# ZYNQ_PL_Bank_35.net
KiCad netlist of a schematic drawn in Altium Designer
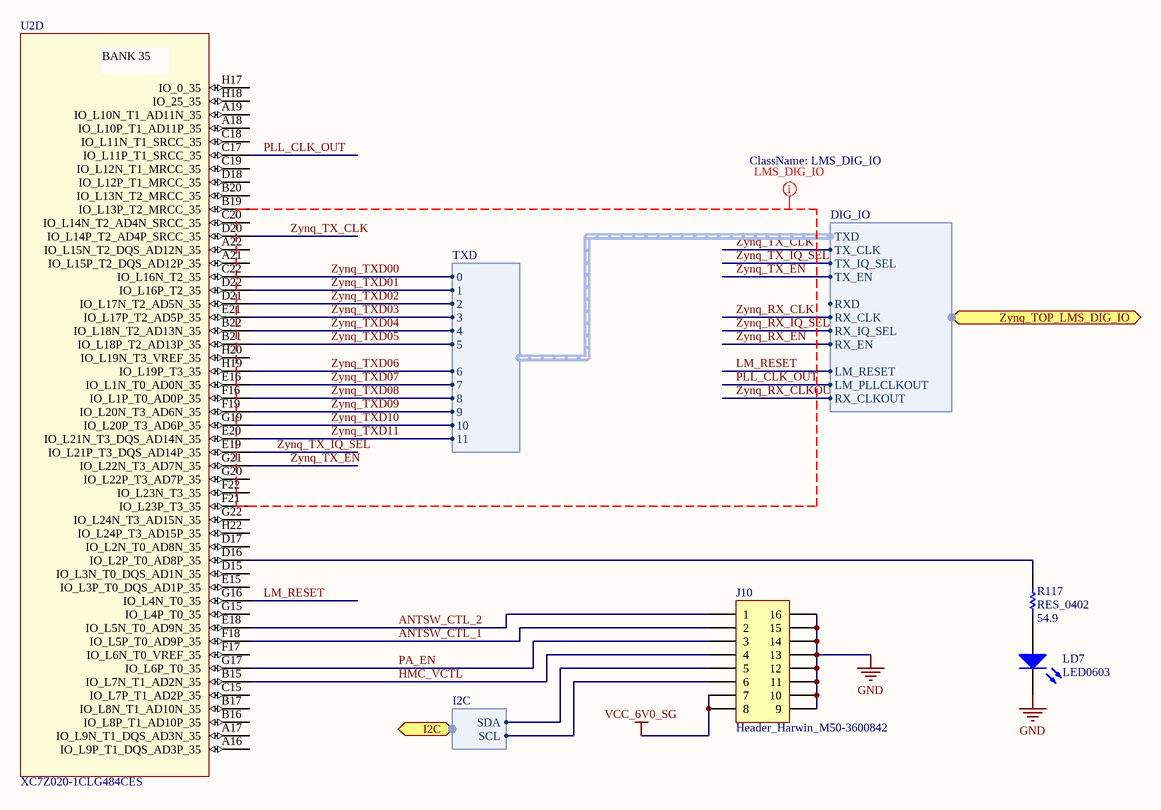
[diagram p0: ZYNQ_PL_Bank_35.SchDoc]

(export (version "E")
  (design (tool "Eeschema 10.0.6"))
  (components
    (comp (ref "J10")
      (value "Header_Harwin_M50-3600842")
      (footprint "Header_Harwin_M50-3600842_16-pos")
      (description "CONN HDR 1.27MM SMD AU 16POS")
      (fields (field (name "PART NUMBER") "M50-3600842") (field (name "MANUFACTURER") "Harwin Inc"))
      (libsource (lib "COMRAD_Database") (part "Header_Harwin_M50-3600842"))
    )
    (comp (ref "LD7")
      (value "LED0603")
      (footprint "LED0603(1608)_HSMG-C190")
      (description "LED 570NM GREEN DIFF 0603 SMD")
      (fields (field (name "PART NUMBER") "\"HSMG-C190\"") (field (name "MANUFACTURER") "Avago"))
      (libsource (lib "COMRAD_Database") (part "LED0603"))
    )
    (comp (ref "R117")
      (value "RES_0402")
      (footprint "RESC0402(1005)_N")
      (description "RES 54.9 OHM 1/10W 1% 0402 SMD")
      (fields
        (field (name "ALTIUM_VALUE") "54.9")
        (field (name "PART NUMBER") "ERJ-2RKF54R9X")
        (field (name "MANUFACTURER") "Panasonic Electronic Components")
      )
      (libsource (lib "COMRAD_Database") (part "RES_0402"))
    )
    (comp (ref "U2")
      (value "XC7Z020-1CLG484CES")
      (footprint "ZYNQ_xc7z020clg484pkg_BGA-484")
      (description "XC7Z020-1CLG484CES, Zynq-7000 All Programmable SoC")
      (fields (field (name "MANUFACTURER") "Xilinx"))
      (libsource (lib "COMRAD_Database") (part "ZYNQ_XC7Z020CLG484PKG"))
    )
  )
  (nets
    (net (code "4") (name "/ANTSW_CTL_1") (class "Default")
      (node (ref "J10") (pin "2") (pinfunction "2_2") (pintype "passive"))
      (node (ref "U2") (pin "F18") (pinfunction "IO_L5P_T0_AD9P_35_F18") (pintype "bidirectional"))
    )
    (net (code "5") (name "/ANTSW_CTL_2") (class "Default")
      (node (ref "J10") (pin "1") (pinfunction "1_1") (pintype "passive"))
      (node (ref "U2") (pin "E18") (pinfunction "IO_L5N_T0_AD9N_35_E18") (pintype "bidirectional"))
    )
    (net (code "6") (name "/HMC_VCTL") (class "Default")
      (node (ref "J10") (pin "4") (pinfunction "4_4") (pintype "passive"))
      (node (ref "U2") (pin "B15") (pinfunction "IO_L7N_T1_AD2N_35_B15") (pintype "bidirectional"))
    )
    (net (code "7") (name "/LM_RESET") (class "Default")
      (node (ref "U2") (pin "G16") (pinfunction "IO_L4N_T0_35_G16") (pintype "bidirectional"))
    )
    (net (code "8") (name "/PA_EN") (class "Default")
      (node (ref "J10") (pin "3") (pinfunction "3_3") (pintype "passive"))
      (node (ref "U2") (pin "G17") (pinfunction "IO_L6P_T0_35_G17") (pintype "bidirectional"))
    )
    (net (code "9") (name "/PLL_CLK_OUT") (class "Default")
      (node (ref "U2") (pin "C17") (pinfunction "IO_L11P_T1_SRCC_35_C17") (pintype "bidirectional"))
    )
    (net (code "10") (name "/SCL") (class "Default")
      (node (ref "J10") (pin "6") (pinfunction "6_6") (pintype "passive"))
    )
    (net (code "11") (name "/SDA") (class "Default")
      (node (ref "J10") (pin "5") (pinfunction "5_5") (pintype "passive"))
    )
    (net (code "17") (name "/Zynq_TXD00") (class "Default")
      (node (ref "U2") (pin "C22") (pinfunction "IO_L16N_T2_35_C22") (pintype "bidirectional"))
    )
    (net (code "18") (name "/Zynq_TXD01") (class "Default")
      (node (ref "U2") (pin "D22") (pinfunction "IO_L16P_T2_35_D22") (pintype "bidirectional"))
    )
    (net (code "19") (name "/Zynq_TXD02") (class "Default")
      (node (ref "U2") (pin "D21") (pinfunction "IO_L17N_T2_AD5N_35_D21") (pintype "bidirectional"))
    )
    (net (code "20") (name "/Zynq_TXD03") (class "Default")
      (node (ref "U2") (pin "E21") (pinfunction "IO_L17P_T2_AD5P_35_E21") (pintype "bidirectional"))
    )
    (net (code "21") (name "/Zynq_TXD04") (class "Default")
      (node (ref "U2") (pin "B22") (pinfunction "IO_L18N_T2_AD13N_35_B22") (pintype "bidirectional"))
    )
    (net (code "22") (name "/Zynq_TXD05") (class "Default")
      (node (ref "U2") (pin "B21") (pinfunction "IO_L18P_T2_AD13P_35_B21") (pintype "bidirectional"))
    )
    (net (code "23") (name "/Zynq_TXD06") (class "Default")
      (node (ref "U2") (pin "H19") (pinfunction "IO_L19P_T3_35_H19") (pintype "bidirectional"))
    )
    (net (code "24") (name "/Zynq_TXD07") (class "Default")
      (node (ref "U2") (pin "E16") (pinfunction "IO_L1N_T0_AD0N_35_E16") (pintype "bidirectional"))
    )
    (net (code "25") (name "/Zynq_TXD08") (class "Default")
      (node (ref "U2") (pin "F16") (pinfunction "IO_L1P_T0_AD0P_35_F16") (pintype "bidirectional"))
    )
    (net (code "26") (name "/Zynq_TXD09") (class "Default")
      (node (ref "U2") (pin "F19") (pinfunction "IO_L20N_T3_AD6N_35_F19") (pintype "bidirectional"))
    )
    (net (code "27") (name "/Zynq_TXD10") (class "Default")
      (node (ref "U2") (pin "G19") (pinfunction "IO_L20P_T3_AD6P_35_G19") (pintype "bidirectional"))
    )
    (net (code "28") (name "/Zynq_TXD11") (class "Default")
      (node (ref "U2") (pin "E20") (pinfunction "IO_L21N_T3_DQS_AD14N_35_E20") (pintype "bidirectional"))
    )
    (net (code "29") (name "/Zynq_TX_CLK") (class "Default")
      (node (ref "U2") (pin "D20") (pinfunction "IO_L14P_T2_AD4P_SRCC_35_D20") (pintype "bidirectional"))
    )
    (net (code "30") (name "/Zynq_TX_EN") (class "Default")
      (node (ref "U2") (pin "G21") (pinfunction "IO_L22N_T3_AD7N_35_G21") (pintype "bidirectional"))
    )
    (net (code "31") (name "/Zynq_TX_IQ_SEL") (class "Default")
      (node (ref "U2") (pin "E19") (pinfunction "IO_L21P_T3_DQS_AD14P_35_E19") (pintype "bidirectional"))
    )
    (net (code "34") (name "GND") (class "Default")
      (node (ref "J10") (pin "10") (pinfunction "10_10") (pintype "passive"))
      (node (ref "J10") (pin "11") (pinfunction "11_11") (pintype "passive"))
      (node (ref "J10") (pin "12") (pinfunction "12_12") (pintype "passive"))
      (node (ref "J10") (pin "13") (pinfunction "13_13") (pintype "passive"))
      (node (ref "J10") (pin "14") (pinfunction "14_14") (pintype "passive"))
      (node (ref "J10") (pin "15") (pinfunction "15_15") (pintype "passive"))
      (node (ref "J10") (pin "16") (pinfunction "16_16") (pintype "passive"))
      (node (ref "J10") (pin "9") (pinfunction "9_9") (pintype "passive"))
      (node (ref "LD7") (pin "1") (pinfunction "K_1") (pintype "passive"))
    )
    (net (code "35") (name "Net-(LD7-A)") (class "Default")
      (node (ref "LD7") (pin "2") (pinfunction "A_2") (pintype "passive"))
      (node (ref "R117") (pin "1") (pinfunction "1_1") (pintype "passive"))
    )
    (net (code "36") (name "Net-(U2D-IO_L2P_T0_AD8P_35)") (class "Default")
      (node (ref "R117") (pin "2") (pinfunction "2_2") (pintype "passive"))
      (node (ref "U2") (pin "D16") (pinfunction "IO_L2P_T0_AD8P_35_D16") (pintype "bidirectional"))
    )
    (net (code "37") (name "VCC_6V0_SG") (class "Default")
      (node (ref "J10") (pin "7") (pinfunction "7_7") (pintype "passive"))
      (node (ref "J10") (pin "8") (pinfunction "8_8") (pintype "passive"))
    )
    (net (code "38") (name "unconnected-(U2D-IO_0_35-PadH17)") (class "Default")
      (node (ref "U2") (pin "H17") (pinfunction "IO_0_35_H17") (pintype "bidirectional"))
    )
    (net (code "39") (name "unconnected-(U2D-IO_25_35-PadH18)") (class "Default")
      (node (ref "U2") (pin "H18") (pinfunction "IO_25_35_H18") (pintype "bidirectional"))
    )
    (net (code "40") (name "unconnected-(U2D-IO_L2N_T0_AD8N_35-PadD17)") (class "Default")
      (node (ref "U2") (pin "D17") (pinfunction "IO_L2N_T0_AD8N_35_D17") (pintype "bidirectional"))
    )
    (net (code "41") (name "unconnected-(U2D-IO_L3N_T0_DQS_AD1N_35-PadD15)") (class "Default")
      (node (ref "U2") (pin "D15") (pinfunction "IO_L3N_T0_DQS_AD1N_35_D15") (pintype "bidirectional"))
    )
    (net (code "42") (name "unconnected-(U2D-IO_L3P_T0_DQS_AD1P_35-PadE15)") (class "Default")
      (node (ref "U2") (pin "E15") (pinfunction "IO_L3P_T0_DQS_AD1P_35_E15") (pintype "bidirectional"))
    )
    (net (code "43") (name "unconnected-(U2D-IO_L4P_T0_35-PadG15)") (class "Default")
      (node (ref "U2") (pin "G15") (pinfunction "IO_L4P_T0_35_G15") (pintype "bidirectional"))
    )
    (net (code "44") (name "unconnected-(U2D-IO_L6N_T0_VREF_35-PadF17)") (class "Default")
      (node (ref "U2") (pin "F17") (pinfunction "IO_L6N_T0_VREF_35_F17") (pintype "bidirectional"))
    )
    (net (code "45") (name "unconnected-(U2D-IO_L7P_T1_AD2P_35-PadC15)") (class "Default")
      (node (ref "U2") (pin "C15") (pinfunction "IO_L7P_T1_AD2P_35_C15") (pintype "bidirectional"))
    )
    (net (code "46") (name "unconnected-(U2D-IO_L8N_T1_AD10N_35-PadB17)") (class "Default")
      (node (ref "U2") (pin "B17") (pinfunction "IO_L8N_T1_AD10N_35_B17") (pintype "bidirectional"))
    )
    (net (code "47") (name "unconnected-(U2D-IO_L8P_T1_AD10P_35-PadB16)") (class "Default")
      (node (ref "U2") (pin "B16") (pinfunction "IO_L8P_T1_AD10P_35_B16") (pintype "bidirectional"))
    )
    (net (code "48") (name "unconnected-(U2D-IO_L9N_T1_DQS_AD3N_35-PadA17)") (class "Default")
      (node (ref "U2") (pin "A17") (pinfunction "IO_L9N_T1_DQS_AD3N_35_A17") (pintype "bidirectional"))
    )
    (net (code "49") (name "unconnected-(U2D-IO_L9P_T1_DQS_AD3P_35-PadA16)") (class "Default")
      (node (ref "U2") (pin "A16") (pinfunction "IO_L9P_T1_DQS_AD3P_35_A16") (pintype "bidirectional"))
    )
    (net (code "50") (name "unconnected-(U2D-IO_L10N_T1_AD11N_35-PadA19)") (class "Default")
      (node (ref "U2") (pin "A19") (pinfunction "IO_L10N_T1_AD11N_35_A19") (pintype "bidirectional"))
    )
    (net (code "51") (name "unconnected-(U2D-IO_L10P_T1_AD11P_35-PadA18)") (class "Default")
      (node (ref "U2") (pin "A18") (pinfunction "IO_L10P_T1_AD11P_35_A18") (pintype "bidirectional"))
    )
    (net (code "52") (name "unconnected-(U2D-IO_L11N_T1_SRCC_35-PadC18)") (class "Default")
      (node (ref "U2") (pin "C18") (pinfunction "IO_L11N_T1_SRCC_35_C18") (pintype "bidirectional"))
    )
    (net (code "53") (name "unconnected-(U2D-IO_L12N_T1_MRCC_35-PadC19)") (class "Default")
      (node (ref "U2") (pin "C19") (pinfunction "IO_L12N_T1_MRCC_35_C19") (pintype "bidirectional"))
    )
    (net (code "54") (name "unconnected-(U2D-IO_L12P_T1_MRCC_35-PadD18)") (class "Default")
      (node (ref "U2") (pin "D18") (pinfunction "IO_L12P_T1_MRCC_35_D18") (pintype "bidirectional"))
    )
    (net (code "55") (name "unconnected-(U2D-IO_L13N_T2_MRCC_35-PadB20)") (class "Default")
      (node (ref "U2") (pin "B20") (pinfunction "IO_L13N_T2_MRCC_35_B20") (pintype "bidirectional"))
    )
    (net (code "56") (name "unconnected-(U2D-IO_L13P_T2_MRCC_35-PadB19)") (class "Default")
      (node (ref "U2") (pin "B19") (pinfunction "IO_L13P_T2_MRCC_35_B19") (pintype "bidirectional"))
    )
    (net (code "57") (name "unconnected-(U2D-IO_L14N_T2_AD4N_SRCC_35-PadC20)") (class "Default")
      (node (ref "U2") (pin "C20") (pinfunction "IO_L14N_T2_AD4N_SRCC_35_C20") (pintype "bidirectional"))
    )
    (net (code "58") (name "unconnected-(U2D-IO_L15N_T2_DQS_AD12N_35-PadA22)") (class "Default")
      (node (ref "U2") (pin "A22") (pinfunction "IO_L15N_T2_DQS_AD12N_35_A22") (pintype "bidirectional"))
    )
    (net (code "59") (name "unconnected-(U2D-IO_L15P_T2_DQS_AD12P_35-PadA21)") (class "Default")
      (node (ref "U2") (pin "A21") (pinfunction "IO_L15P_T2_DQS_AD12P_35_A21") (pintype "bidirectional"))
    )
    (net (code "60") (name "unconnected-(U2D-IO_L19N_T3_VREF_35-PadH20)") (class "Default")
      (node (ref "U2") (pin "H20") (pinfunction "IO_L19N_T3_VREF_35_H20") (pintype "bidirectional"))
    )
    (net (code "61") (name "unconnected-(U2D-IO_L22P_T3_AD7P_35-PadG20)") (class "Default")
      (node (ref "U2") (pin "G20") (pinfunction "IO_L22P_T3_AD7P_35_G20") (pintype "bidirectional"))
    )
    (net (code "62") (name "unconnected-(U2D-IO_L23N_T3_35-PadF22)") (class "Default")
      (node (ref "U2") (pin "F22") (pinfunction "IO_L23N_T3_35_F22") (pintype "bidirectional"))
    )
    (net (code "63") (name "unconnected-(U2D-IO_L23P_T3_35-PadF21)") (class "Default")
      (node (ref "U2") (pin "F21") (pinfunction "IO_L23P_T3_35_F21") (pintype "bidirectional"))
    )
    (net (code "64") (name "unconnected-(U2D-IO_L24N_T3_AD15N_35-PadG22)") (class "Default")
      (node (ref "U2") (pin "G22") (pinfunction "IO_L24N_T3_AD15N_35_G22") (pintype "bidirectional"))
    )
    (net (code "65") (name "unconnected-(U2D-IO_L24P_T3_AD15P_35-PadH22)") (class "Default")
      (node (ref "U2") (pin "H22") (pinfunction "IO_L24P_T3_AD15P_35_H22") (pintype "bidirectional"))
    )
  )
)
